# Charging.net
KiCad netlist of a schematic drawn in Altium Designer
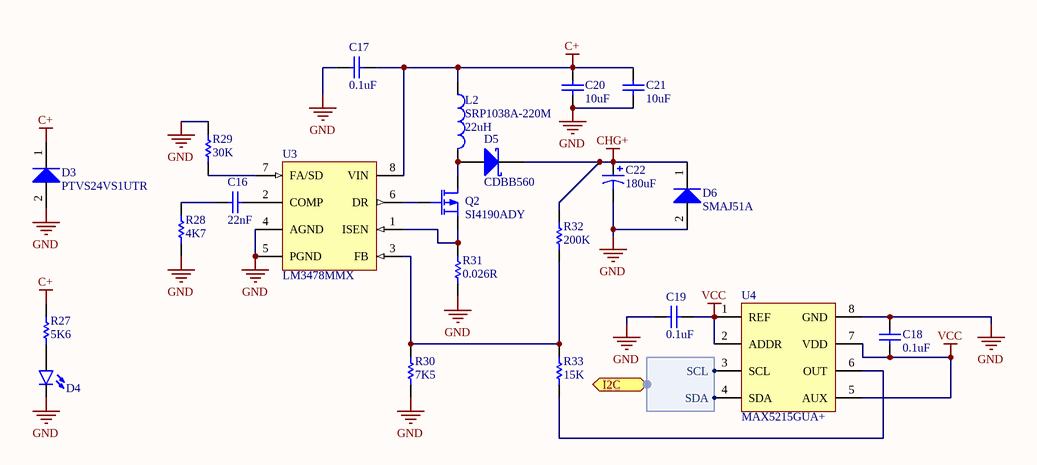
[diagram p0: Charging.SchDoc]

(export (version "E")
  (design (tool "Eeschema 10.0.6"))
  (components
    (comp (ref "C16")
      (value "22nF")
      (footprint "C0402[1005X55]")
      (description "22nF 50V 10% 0402 (1005 Metric)")
      (fields (field (name "TOLERANCE") "10%") (field (name "PARTNUMBER") "GRM155R71H223KA12J"))
      (libsource (lib "Capacitors") (part "CAP_22nF_50V_0402_10%"))
    )
    (comp (ref "C17")
      (value "0.1uF")
      (footprint "C0402[1005X55]")
      (description "0.1uF 100V 10% 0402 (1005 Metric)")
      (fields (field (name "PARTNUMBER") "GRM155R62A104KE14D") (field (name "MANUFACTURER") "Murata"))
      (libsource (lib "Capacitors") (part "CAP_0.1uF_100V_0402_10%"))
    )
    (comp (ref "C18")
      (value "0.1uF")
      (footprint "C0402[1005X55]")
      (description "0.1uF 6.3V 10% 0402 (1005 Metric)")
      (fields (field (name "PARTNUMBER") "GRM155R70J104KA01D") (field (name "MANUFACTURER") "Murata"))
      (libsource (lib "Capacitors") (part "CAP_0.1uF_6.3V_0402_10%"))
    )
    (comp (ref "C19")
      (value "0.1uF")
      (footprint "C0402[1005X55]")
      (description "0.1uF 6.3V 10% 0402 (1005 Metric)")
      (fields (field (name "PARTNUMBER") "GRM155R70J104KA01D") (field (name "MANUFACTURER") "Murata"))
      (libsource (lib "Capacitors") (part "CAP_0.1uF_6.3V_0402_10%"))
    )
    (comp (ref "C20")
      (value "10uF")
      (footprint "C1206[3216X160]")
      (description "10uF 50V 20% 1206 (3216 Metric)")
      (fields (field (name "TOLERANCE") "20%") (field (name "PARTNUMBER") "UMK316BBJ106ML-T"))
      (libsource (lib "Capacitors") (part "CAP_10uF_50V_1206_20%"))
    )
    (comp (ref "C21")
      (value "10uF")
      (footprint "C1206[3216X160]")
      (description "10uF 50V 20% 1206 (3216 Metric)")
      (fields (field (name "TOLERANCE") "20%") (field (name "PARTNUMBER") "UMK316BBJ106ML-T"))
      (libsource (lib "Capacitors") (part "CAP_10uF_50V_1206_20%"))
    )
    (comp (ref "C22")
      (value "180uF")
      (footprint "CAP-ELECTROLYTIC[10.0x12.6]")
      (description "180uF 50V 20%")
      (fields (field (name "PARTNUMBER") "PCR1H181MCL1GS") (field (name "MANUFACTURER") "Nichicon"))
      (libsource (lib "Capacitors") (part "CAP_180uF_50V_20%"))
    )
    (comp (ref "D3")
      (value "PTVS24VS1UTR")
      (footprint "SOD-123W")
      (fields (field (name "PARTNUMBER") "PTVS24VS1UTR,115") (field (name "MANUFACTURER") "NXP"))
      (libsource (lib "Diodes") (part "PTVS24VS1UTR,115"))
    )
    (comp (ref "D4")
      (value "LED_0603_GREEN_5mA")
      (footprint "LED0603")
      (fields (field (name "PARTNUMBER") "LTST-C193TGKT-5A") (field (name "MANUFACTURER") "Lite-On Inc."))
      (libsource (lib "LEDs") (part "LED_0603_GREEN_5mA"))
    )
    (comp (ref "D5")
      (value "CDBB560")
      (footprint "DO-214AA")
      (fields (field (name "PARTNUMBER") "CDBB560-HF") (field (name "MANUFACTURER") "Comchip Technology"))
      (libsource (lib "Diodes") (part "CDBB560-HF"))
    )
    (comp (ref "D6")
      (value "SMAJ51A")
      (footprint "DO-214AC")
      (fields (field (name "PARTNUMBER") "SMAJ51A-E3/61") (field (name "MANUFACTURER") "Vishay"))
      (libsource (lib "Diodes") (part "SMAJ51A-E3/61"))
    )
    (comp (ref "L2")
      (value "SRP1038A-220M")
      (footprint "SRP1038A")
      (description "22uH 20% 7A 1038")
      (fields (field (name "ALTIUM_VALUE") "22uH") (field (name "MANUFACTURER") "Bourns"))
      (libsource (lib "Inductors") (part "SRP1038A-220M"))
    )
    (comp (ref "Q2")
      (value "SI4190ADY")
      (footprint "SO-8")
      (description "N-Channel MOSFET")
      (fields (field (name "PARTNUMBER") "SI4190ADY-T1-GE3") (field (name "MANUFACTURER") "Vishay"))
      (libsource (lib "MOSFETs") (part "SI4190ADY-T1-GE3"))
    )
    (comp (ref "R27")
      (value "5K6")
      (footprint "R0402[1005]")
      (description "5K6 0.063W 1% 0402 (1005 Metric)")
      (fields (field (name "POWER") "0.063W") (field (name "TOLERANCE") "1%"))
      (libsource (lib "Resistors") (part "RES_5K6_0402_1%"))
    )
    (comp (ref "R28")
      (value "4K7")
      (footprint "R0402[1005]")
      (description "4K7 0.063W 1% 0402 (1005 Metric)")
      (fields (field (name "TOLERANCE") "1%") (field (name "POWER") "0.063W"))
      (libsource (lib "Resistors") (part "RES_4K7_0402_1%"))
    )
    (comp (ref "R29")
      (value "30K")
      (footprint "R0402[1005]")
      (description "30K 0.063W 1% 0402 (1005 Metric)")
      (fields (field (name "TOLERANCE") "1%") (field (name "POWER") "0.063W"))
      (libsource (lib "Resistors") (part "RES_30K_0402_1%"))
    )
    (comp (ref "R30")
      (value "7K5")
      (footprint "R0402[1005]")
      (description "7K5 0.063W 1% 0402 (1005 Metric)")
      (fields (field (name "POWER") "0.063W") (field (name "TOLERANCE") "1%"))
      (libsource (lib "Resistors") (part "RES_7K5_0402_1%"))
    )
    (comp (ref "R31")
      (value "0.026R")
      (footprint "R1206[3216]")
      (description "0.026R 1W 1% 1206 (3216 Metric)")
      (fields (field (name "POWER") "1W") (field (name "TOLERANCE") "1%"))
      (libsource (lib "Resistors") (part "RES_0.026R_1206_1%"))
    )
    (comp (ref "R32")
      (value "200K")
      (footprint "R0402[1005]")
      (description "200K 0.063W 1% 0402 (1005 Metric)")
      (fields (field (name "POWER") "0.063W") (field (name "TOLERANCE") "1%"))
      (libsource (lib "Resistors") (part "RES_200K_0402_1%"))
    )
    (comp (ref "R33")
      (value "15K")
      (footprint "R0402[1005]")
      (description "15K 0.063W 1% 0402 (1005 Metric)")
      (fields (field (name "MANUFACTURER") "KOA Speer") (field (name "PARTNUMBER") "RK73H1ETTP1502F"))
      (libsource (lib "Resistors") (part "RES_15K_0402_1%"))
    )
    (comp (ref "U3")
      (value "LM3478MMX")
      (footprint "MSOP-8")
      (fields (field (name "MANUFACTURER") "Texas Instruments") (field (name "PARTNUMBER") "LM3478MMX/NOPB"))
      (libsource (lib "ICs") (part "LM3478MMX"))
    )
    (comp (ref "U4")
      (value "MAX5215GUA+")
      (footprint "MSOP-8")
      (description "14 Bit Digital to Analog Converter")
      (fields (field (name "MANUFACTURER") "Maxim Integrated"))
      (libsource (lib "ICs") (part "MAX5215GUA+"))
    )
  )
  (nets
    (net (code "2") (name "/SCL") (class "Default")
      (node (ref "U4") (pin "3") (pinfunction "SCL_3") (pintype "passive"))
    )
    (net (code "3") (name "/SDA") (class "Default")
      (node (ref "U4") (pin "4") (pinfunction "SDA_4") (pintype "passive"))
    )
    (net (code "5") (name "C+") (class "Default")
      (node (ref "C17") (pin "2") (pinfunction "2_2") (pintype "passive"))
      (node (ref "C20") (pin "2") (pinfunction "2_2") (pintype "passive"))
      (node (ref "C21") (pin "2") (pinfunction "2_2") (pintype "passive"))
      (node (ref "D3") (pin "1") (pinfunction "K_1") (pintype "passive"))
      (node (ref "L2") (pin "1") (pinfunction "1_1") (pintype "passive"))
      (node (ref "R27") (pin "2") (pinfunction "2_2") (pintype "passive"))
      (node (ref "U3") (pin "8") (pinfunction "VIN_8") (pintype "power_in"))
    )
    (net (code "6") (name "CHG+") (class "Default")
      (node (ref "C22") (pin "1") (pinfunction "1_1") (pintype "passive"))
      (node (ref "D5") (pin "2") (pinfunction "K_2") (pintype "passive"))
      (node (ref "D6") (pin "1") (pinfunction "K_1") (pintype "passive"))
      (node (ref "R32") (pin "2") (pinfunction "2_2") (pintype "passive"))
    )
    (net (code "7") (name "GND") (class "Default")
      (node (ref "C17") (pin "1") (pinfunction "1_1") (pintype "passive"))
      (node (ref "C18") (pin "1") (pinfunction "1_1") (pintype "passive"))
      (node (ref "C19") (pin "1") (pinfunction "1_1") (pintype "passive"))
      (node (ref "C20") (pin "1") (pinfunction "1_1") (pintype "passive"))
      (node (ref "C21") (pin "1") (pinfunction "1_1") (pintype "passive"))
      (node (ref "C22") (pin "2") (pinfunction "2_2") (pintype "passive"))
      (node (ref "D3") (pin "2") (pinfunction "A_2") (pintype "passive"))
      (node (ref "D4") (pin "C") (pinfunction "C_C") (pintype "passive"))
      (node (ref "D6") (pin "2") (pinfunction "A_2") (pintype "passive"))
      (node (ref "R28") (pin "1") (pinfunction "1_1") (pintype "passive"))
      (node (ref "R29") (pin "2") (pinfunction "2_2") (pintype "passive"))
      (node (ref "R30") (pin "1") (pinfunction "1_1") (pintype "passive"))
      (node (ref "R31") (pin "1") (pinfunction "1_1") (pintype "passive"))
      (node (ref "U3") (pin "4") (pinfunction "AGND_4") (pintype "power_in"))
      (node (ref "U3") (pin "5") (pinfunction "PGND_5") (pintype "power_in"))
      (node (ref "U4") (pin "8") (pinfunction "GND_8") (pintype "power_in"))
    )
    (net (code "8") (name "Net-(C16-Pad1)") (class "Default")
      (node (ref "C16") (pin "1") (pinfunction "1_1") (pintype "passive"))
      (node (ref "R28") (pin "2") (pinfunction "2_2") (pintype "passive"))
    )
    (net (code "9") (name "Net-(D4-PadA)") (class "Default")
      (node (ref "D4") (pin "A") (pinfunction "A_A") (pintype "passive"))
      (node (ref "R27") (pin "1") (pinfunction "1_1") (pintype "passive"))
    )
    (net (code "10") (name "Net-(D5-A)") (class "Default")
      (node (ref "D5") (pin "1") (pinfunction "A_1") (pintype "passive"))
      (node (ref "L2") (pin "2") (pinfunction "2_2") (pintype "passive"))
      (node (ref "Q2") (pin "3") (pinfunction "D_3") (pintype "passive"))
    )
    (net (code "11") (name "Net-(Q2-G)") (class "Default")
      (node (ref "Q2") (pin "2") (pinfunction "G_2") (pintype "passive"))
      (node (ref "U3") (pin "6") (pinfunction "DR_6") (pintype "output"))
    )
    (net (code "12") (name "Net-(Q2-S)") (class "Default")
      (node (ref "Q2") (pin "1") (pinfunction "S_1") (pintype "passive"))
      (node (ref "R31") (pin "2") (pinfunction "2_2") (pintype "passive"))
      (node (ref "U3") (pin "1") (pinfunction "ISEN_1") (pintype "input"))
    )
    (net (code "13") (name "Net-(U3-COMP)") (class "Default")
      (node (ref "C16") (pin "2") (pinfunction "2_2") (pintype "passive"))
      (node (ref "U3") (pin "2") (pinfunction "COMP_2") (pintype "passive"))
    )
    (net (code "14") (name "Net-(U3-FA{slash}SD)") (class "Default")
      (node (ref "R29") (pin "1") (pinfunction "1_1") (pintype "passive"))
      (node (ref "U3") (pin "7") (pinfunction "FA/SD_7") (pintype "input"))
    )
    (net (code "15") (name "Net-(U3-FB)") (class "Default")
      (node (ref "R30") (pin "2") (pinfunction "2_2") (pintype "passive"))
      (node (ref "R32") (pin "1") (pinfunction "1_1") (pintype "passive"))
      (node (ref "R33") (pin "2") (pinfunction "2_2") (pintype "passive"))
      (node (ref "U3") (pin "3") (pinfunction "FB_3") (pintype "input"))
    )
    (net (code "16") (name "Net-(U4-OUT)") (class "Default")
      (node (ref "R33") (pin "1") (pinfunction "1_1") (pintype "passive"))
      (node (ref "U4") (pin "6") (pinfunction "OUT_6") (pintype "passive"))
    )
    (net (code "17") (name "VCC") (class "Default")
      (node (ref "C18") (pin "2") (pinfunction "2_2") (pintype "passive"))
      (node (ref "C19") (pin "2") (pinfunction "2_2") (pintype "passive"))
      (node (ref "U4") (pin "1") (pinfunction "REF_1") (pintype "passive"))
      (node (ref "U4") (pin "2") (pinfunction "ADDR_2") (pintype "passive"))
      (node (ref "U4") (pin "5") (pinfunction "AUX_5") (pintype "passive"))
      (node (ref "U4") (pin "7") (pinfunction "VDD_7") (pintype "power_in"))
    )
  )
)
